# exo_sequencer.net
KiCad netlist of a schematic drawn in EAGLE
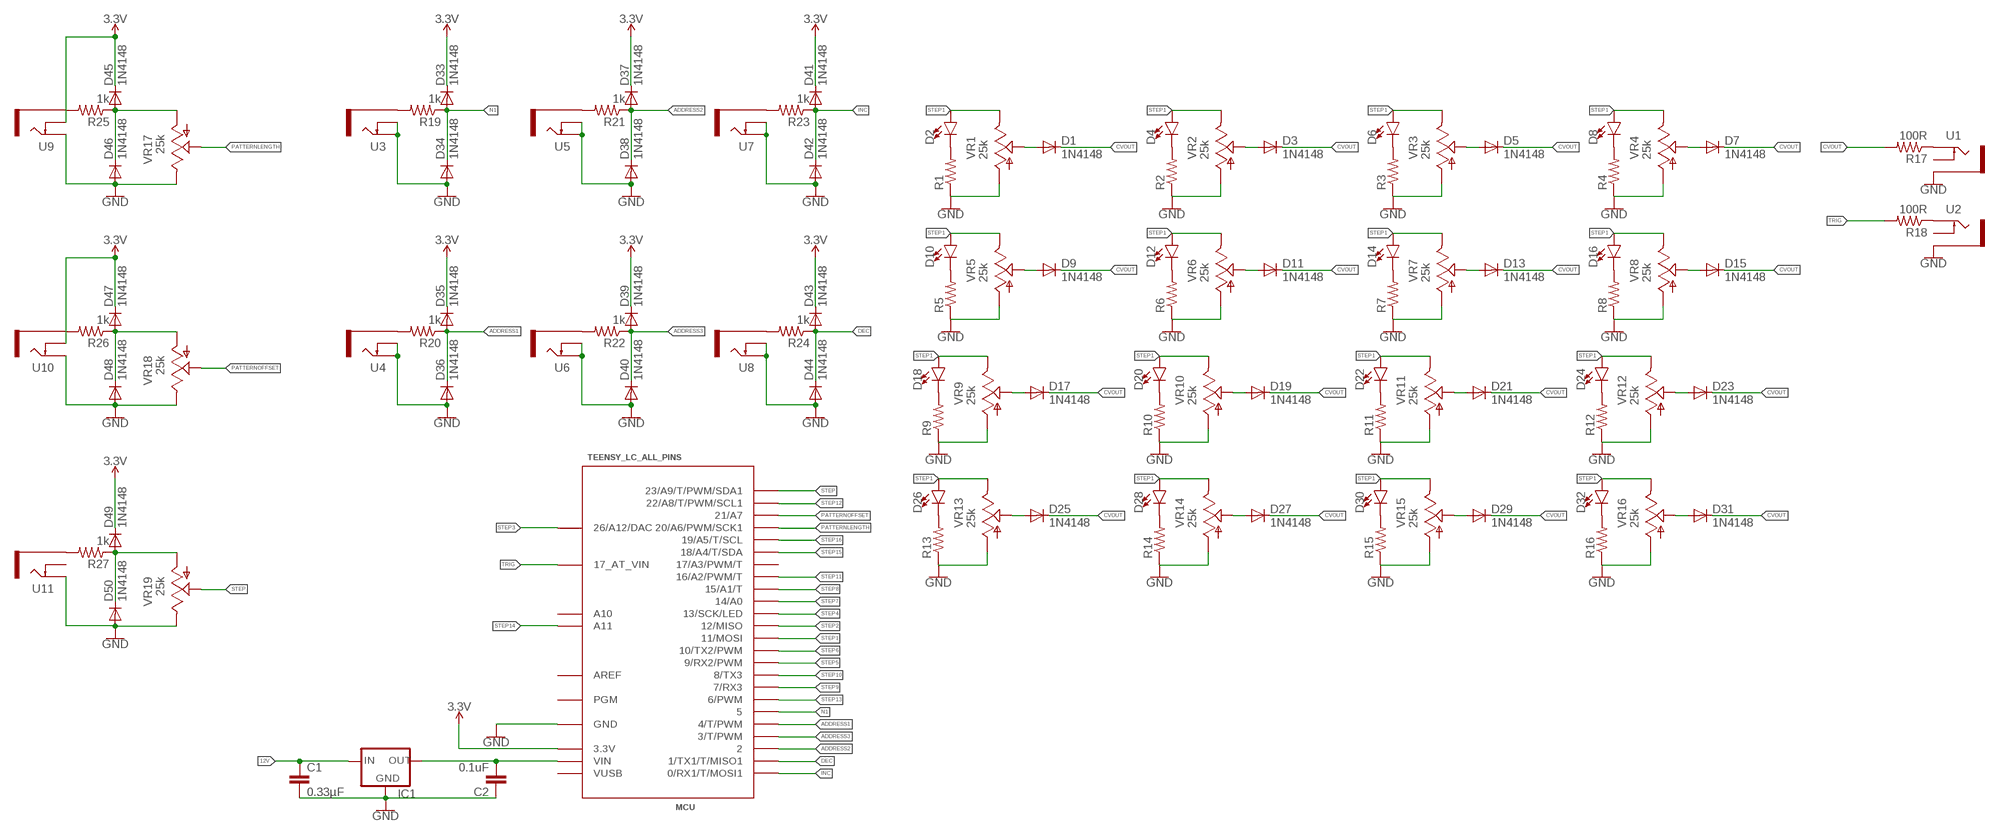
[diagram p0: schematic, sheet 1]

(export (version "E")
  (design (tool "Eeschema 10.0.6"))
  (components
    (comp (ref "C1")
      (value "0.33µF")
      (footprint "eagle-import:0805")
      (libsource (lib "eagle-import") (part "0.33UF/330NF-0805-50V-10%"))
    )
    (comp (ref "C2")
      (value "0.1uF")
      (footprint "eagle-import:0402")
      (libsource (lib "eagle-import") (part "0.1UF-0402-16V-10%"))
    )
    (comp (ref "D1")
      (value "1N4148")
      (footprint "eagle-import:DO35-7")
      (libsource (lib "eagle-import") (part "SMALL_DIODEDO35-7"))
    )
    (comp (ref "D2")
      (value "LED-3MM-NO_SILK")
      (footprint "eagle-import:LED_3MM-NS")
      (libsource (lib "eagle-import") (part "LED-3MM-NO_SILK"))
    )
    (comp (ref "D3")
      (value "1N4148")
      (footprint "eagle-import:DO35-7")
      (libsource (lib "eagle-import") (part "SMALL_DIODEDO35-7"))
    )
    (comp (ref "D4")
      (value "LED-3MM-NO_SILK")
      (footprint "eagle-import:LED_3MM-NS")
      (libsource (lib "eagle-import") (part "LED-3MM-NO_SILK"))
    )
    (comp (ref "D5")
      (value "1N4148")
      (footprint "eagle-import:DO35-7")
      (libsource (lib "eagle-import") (part "SMALL_DIODEDO35-7"))
    )
    (comp (ref "D6")
      (value "LED-3MM-NO_SILK")
      (footprint "eagle-import:LED_3MM-NS")
      (libsource (lib "eagle-import") (part "LED-3MM-NO_SILK"))
    )
    (comp (ref "D7")
      (value "1N4148")
      (footprint "eagle-import:DO35-7")
      (libsource (lib "eagle-import") (part "SMALL_DIODEDO35-7"))
    )
    (comp (ref "D8")
      (value "LED-3MM-NO_SILK")
      (footprint "eagle-import:LED_3MM-NS")
      (libsource (lib "eagle-import") (part "LED-3MM-NO_SILK"))
    )
    (comp (ref "D9")
      (value "1N4148")
      (footprint "eagle-import:DO35-7")
      (libsource (lib "eagle-import") (part "SMALL_DIODEDO35-7"))
    )
    (comp (ref "D10")
      (value "LED-3MM-NO_SILK")
      (footprint "eagle-import:LED_3MM-NS")
      (libsource (lib "eagle-import") (part "LED-3MM-NO_SILK"))
    )
    (comp (ref "D11")
      (value "1N4148")
      (footprint "eagle-import:DO35-7")
      (libsource (lib "eagle-import") (part "SMALL_DIODEDO35-7"))
    )
    (comp (ref "D12")
      (value "LED-3MM-NO_SILK")
      (footprint "eagle-import:LED_3MM-NS")
      (libsource (lib "eagle-import") (part "LED-3MM-NO_SILK"))
    )
    (comp (ref "D13")
      (value "1N4148")
      (footprint "eagle-import:DO35-7")
      (libsource (lib "eagle-import") (part "SMALL_DIODEDO35-7"))
    )
    (comp (ref "D14")
      (value "LED-3MM-NO_SILK")
      (footprint "eagle-import:LED_3MM-NS")
      (libsource (lib "eagle-import") (part "LED-3MM-NO_SILK"))
    )
    (comp (ref "D15")
      (value "1N4148")
      (footprint "eagle-import:DO35-7")
      (libsource (lib "eagle-import") (part "SMALL_DIODEDO35-7"))
    )
    (comp (ref "D16")
      (value "LED-3MM-NO_SILK")
      (footprint "eagle-import:LED_3MM-NS")
      (libsource (lib "eagle-import") (part "LED-3MM-NO_SILK"))
    )
    (comp (ref "D17")
      (value "1N4148")
      (footprint "eagle-import:DO35-7")
      (libsource (lib "eagle-import") (part "SMALL_DIODEDO35-7"))
    )
    (comp (ref "D18")
      (value "LED-3MM-NO_SILK")
      (footprint "eagle-import:LED_3MM-NS")
      (libsource (lib "eagle-import") (part "LED-3MM-NO_SILK"))
    )
    (comp (ref "D19")
      (value "1N4148")
      (footprint "eagle-import:DO35-7")
      (libsource (lib "eagle-import") (part "SMALL_DIODEDO35-7"))
    )
    (comp (ref "D20")
      (value "LED-3MM-NO_SILK")
      (footprint "eagle-import:LED_3MM-NS")
      (libsource (lib "eagle-import") (part "LED-3MM-NO_SILK"))
    )
    (comp (ref "D21")
      (value "1N4148")
      (footprint "eagle-import:DO35-7")
      (libsource (lib "eagle-import") (part "SMALL_DIODEDO35-7"))
    )
    (comp (ref "D22")
      (value "LED-3MM-NO_SILK")
      (footprint "eagle-import:LED_3MM-NS")
      (libsource (lib "eagle-import") (part "LED-3MM-NO_SILK"))
    )
    (comp (ref "D23")
      (value "1N4148")
      (footprint "eagle-import:DO35-7")
      (libsource (lib "eagle-import") (part "SMALL_DIODEDO35-7"))
    )
    (comp (ref "D24")
      (value "LED-3MM-NO_SILK")
      (footprint "eagle-import:LED_3MM-NS")
      (libsource (lib "eagle-import") (part "LED-3MM-NO_SILK"))
    )
    (comp (ref "D25")
      (value "1N4148")
      (footprint "eagle-import:DO35-7")
      (libsource (lib "eagle-import") (part "SMALL_DIODEDO35-7"))
    )
    (comp (ref "D26")
      (value "LED-3MM-NO_SILK")
      (footprint "eagle-import:LED_3MM-NS")
      (libsource (lib "eagle-import") (part "LED-3MM-NO_SILK"))
    )
    (comp (ref "D27")
      (value "1N4148")
      (footprint "eagle-import:DO35-7")
      (libsource (lib "eagle-import") (part "SMALL_DIODEDO35-7"))
    )
    (comp (ref "D28")
      (value "LED-3MM-NO_SILK")
      (footprint "eagle-import:LED_3MM-NS")
      (libsource (lib "eagle-import") (part "LED-3MM-NO_SILK"))
    )
    (comp (ref "D29")
      (value "1N4148")
      (footprint "eagle-import:DO35-7")
      (libsource (lib "eagle-import") (part "SMALL_DIODEDO35-7"))
    )
    (comp (ref "D30")
      (value "LED-3MM-NO_SILK")
      (footprint "eagle-import:LED_3MM-NS")
      (libsource (lib "eagle-import") (part "LED-3MM-NO_SILK"))
    )
    (comp (ref "D31")
      (value "1N4148")
      (footprint "eagle-import:DO35-7")
      (libsource (lib "eagle-import") (part "SMALL_DIODEDO35-7"))
    )
    (comp (ref "D32")
      (value "LED-3MM-NO_SILK")
      (footprint "eagle-import:LED_3MM-NS")
      (libsource (lib "eagle-import") (part "LED-3MM-NO_SILK"))
    )
    (comp (ref "D33")
      (value "1N4148")
      (footprint "eagle-import:DO35-7")
      (libsource (lib "eagle-import") (part "SMALL_DIODEDO35-7"))
    )
    (comp (ref "D34")
      (value "1N4148")
      (footprint "eagle-import:DO35-7")
      (libsource (lib "eagle-import") (part "SMALL_DIODEDO35-7"))
    )
    (comp (ref "D35")
      (value "1N4148")
      (footprint "eagle-import:DO35-7")
      (libsource (lib "eagle-import") (part "SMALL_DIODEDO35-7"))
    )
    (comp (ref "D36")
      (value "1N4148")
      (footprint "eagle-import:DO35-7")
      (libsource (lib "eagle-import") (part "SMALL_DIODEDO35-7"))
    )
    (comp (ref "D37")
      (value "1N4148")
      (footprint "eagle-import:DO35-7")
      (libsource (lib "eagle-import") (part "SMALL_DIODEDO35-7"))
    )
    (comp (ref "D38")
      (value "1N4148")
      (footprint "eagle-import:DO35-7")
      (libsource (lib "eagle-import") (part "SMALL_DIODEDO35-7"))
    )
    (comp (ref "D39")
      (value "1N4148")
      (footprint "eagle-import:DO35-7")
      (libsource (lib "eagle-import") (part "SMALL_DIODEDO35-7"))
    )
    (comp (ref "D40")
      (value "1N4148")
      (footprint "eagle-import:DO35-7")
      (libsource (lib "eagle-import") (part "SMALL_DIODEDO35-7"))
    )
    (comp (ref "D41")
      (value "1N4148")
      (footprint "eagle-import:DO35-7")
      (libsource (lib "eagle-import") (part "SMALL_DIODEDO35-7"))
    )
    (comp (ref "D42")
      (value "1N4148")
      (footprint "eagle-import:DO35-7")
      (libsource (lib "eagle-import") (part "SMALL_DIODEDO35-7"))
    )
    (comp (ref "D43")
      (value "1N4148")
      (footprint "eagle-import:DO35-7")
      (libsource (lib "eagle-import") (part "SMALL_DIODEDO35-7"))
    )
    (comp (ref "D44")
      (value "1N4148")
      (footprint "eagle-import:DO35-7")
      (libsource (lib "eagle-import") (part "SMALL_DIODEDO35-7"))
    )
    (comp (ref "D45")
      (value "1N4148")
      (footprint "eagle-import:DO35-7")
      (libsource (lib "eagle-import") (part "SMALL_DIODEDO35-7"))
    )
    (comp (ref "D46")
      (value "1N4148")
      (footprint "eagle-import:DO35-7")
      (libsource (lib "eagle-import") (part "SMALL_DIODEDO35-7"))
    )
    (comp (ref "D47")
      (value "1N4148")
      (footprint "eagle-import:DO35-7")
      (libsource (lib "eagle-import") (part "SMALL_DIODEDO35-7"))
    )
    (comp (ref "D48")
      (value "1N4148")
      (footprint "eagle-import:DO35-7")
      (libsource (lib "eagle-import") (part "SMALL_DIODEDO35-7"))
    )
    (comp (ref "D49")
      (value "1N4148")
      (footprint "eagle-import:DO35-7")
      (libsource (lib "eagle-import") (part "SMALL_DIODEDO35-7"))
    )
    (comp (ref "D50")
      (value "1N4148")
      (footprint "eagle-import:DO35-7")
      (libsource (lib "eagle-import") (part "SMALL_DIODEDO35-7"))
    )
    (comp (ref "IC1")
      (value "78MXXL")
      (footprint "eagle-import:78MXXL")
      (libsource (lib "eagle-import") (part "78MXXL"))
    )
    (comp (ref "MCU")
      (value "TEENSY_LC_ALL_PINS")
      (footprint "eagle-import:TEENSY_3.0-3.2&LC_ALL_PINS")
      (libsource (lib "eagle-import") (part "TEENSY_LC_ALL_PINS"))
    )
    (comp (ref "R1")
      (value "R-US_0204/7")
      (footprint "eagle-import:0204_7")
      (libsource (lib "eagle-import") (part "R-US_0204/7"))
    )
    (comp (ref "R2")
      (value "R-US_0204/7")
      (footprint "eagle-import:0204_7")
      (libsource (lib "eagle-import") (part "R-US_0204/7"))
    )
    (comp (ref "R3")
      (value "R-US_0204/7")
      (footprint "eagle-import:0204_7")
      (libsource (lib "eagle-import") (part "R-US_0204/7"))
    )
    (comp (ref "R4")
      (value "R-US_0204/7")
      (footprint "eagle-import:0204_7")
      (libsource (lib "eagle-import") (part "R-US_0204/7"))
    )
    (comp (ref "R5")
      (value "R-US_0204/7")
      (footprint "eagle-import:0204_7")
      (libsource (lib "eagle-import") (part "R-US_0204/7"))
    )
    (comp (ref "R6")
      (value "R-US_0204/7")
      (footprint "eagle-import:0204_7")
      (libsource (lib "eagle-import") (part "R-US_0204/7"))
    )
    (comp (ref "R7")
      (value "R-US_0204/7")
      (footprint "eagle-import:0204_7")
      (libsource (lib "eagle-import") (part "R-US_0204/7"))
    )
    (comp (ref "R8")
      (value "R-US_0204/7")
      (footprint "eagle-import:0204_7")
      (libsource (lib "eagle-import") (part "R-US_0204/7"))
    )
    (comp (ref "R9")
      (value "R-US_0204/7")
      (footprint "eagle-import:0204_7")
      (libsource (lib "eagle-import") (part "R-US_0204/7"))
    )
    (comp (ref "R10")
      (value "R-US_0204/7")
      (footprint "eagle-import:0204_7")
      (libsource (lib "eagle-import") (part "R-US_0204/7"))
    )
    (comp (ref "R11")
      (value "R-US_0204/7")
      (footprint "eagle-import:0204_7")
      (libsource (lib "eagle-import") (part "R-US_0204/7"))
    )
    (comp (ref "R12")
      (value "R-US_0204/7")
      (footprint "eagle-import:0204_7")
      (libsource (lib "eagle-import") (part "R-US_0204/7"))
    )
    (comp (ref "R13")
      (value "R-US_0204/7")
      (footprint "eagle-import:0204_7")
      (libsource (lib "eagle-import") (part "R-US_0204/7"))
    )
    (comp (ref "R14")
      (value "R-US_0204/7")
      (footprint "eagle-import:0204_7")
      (libsource (lib "eagle-import") (part "R-US_0204/7"))
    )
    (comp (ref "R15")
      (value "R-US_0204/7")
      (footprint "eagle-import:0204_7")
      (libsource (lib "eagle-import") (part "R-US_0204/7"))
    )
    (comp (ref "R16")
      (value "R-US_0204/7")
      (footprint "eagle-import:0204_7")
      (libsource (lib "eagle-import") (part "R-US_0204/7"))
    )
    (comp (ref "R17")
      (value "100R")
      (footprint "eagle-import:0204_7")
      (libsource (lib "eagle-import") (part "R-US_0204/7"))
    )
    (comp (ref "R18")
      (value "100R")
      (footprint "eagle-import:0204_7")
      (libsource (lib "eagle-import") (part "R-US_0204/7"))
    )
    (comp (ref "R19")
      (value "1k")
      (footprint "eagle-import:0204_7")
      (libsource (lib "eagle-import") (part "R-US_0204/7"))
    )
    (comp (ref "R20")
      (value "1k")
      (footprint "eagle-import:0204_7")
      (libsource (lib "eagle-import") (part "R-US_0204/7"))
    )
    (comp (ref "R21")
      (value "1k")
      (footprint "eagle-import:0204_7")
      (libsource (lib "eagle-import") (part "R-US_0204/7"))
    )
    (comp (ref "R22")
      (value "1k")
      (footprint "eagle-import:0204_7")
      (libsource (lib "eagle-import") (part "R-US_0204/7"))
    )
    (comp (ref "R23")
      (value "1k")
      (footprint "eagle-import:0204_7")
      (libsource (lib "eagle-import") (part "R-US_0204/7"))
    )
    (comp (ref "R24")
      (value "1k")
      (footprint "eagle-import:0204_7")
      (libsource (lib "eagle-import") (part "R-US_0204/7"))
    )
    (comp (ref "R25")
      (value "1k")
      (footprint "eagle-import:0204_7")
      (libsource (lib "eagle-import") (part "R-US_0204/7"))
    )
    (comp (ref "R26")
      (value "1k")
      (footprint "eagle-import:0204_7")
      (libsource (lib "eagle-import") (part "R-US_0204/7"))
    )
    (comp (ref "R27")
      (value "1k")
      (footprint "eagle-import:0204_7")
      (libsource (lib "eagle-import") (part "R-US_0204/7"))
    )
    (comp (ref "U1")
      (value "THONKICONNNEW")
      (footprint "eagle-import:WQP-PJ301M-12_JACK")
      (libsource (lib "eagle-import") (part "THONKICONNNEW"))
    )
    (comp (ref "U2")
      (value "THONKICONNNEW")
      (footprint "eagle-import:WQP-PJ301M-12_JACK")
      (libsource (lib "eagle-import") (part "THONKICONNNEW"))
    )
    (comp (ref "U3")
      (value "THONKICONNNEW")
      (footprint "eagle-import:WQP-PJ301M-12_JACK")
      (libsource (lib "eagle-import") (part "THONKICONNNEW"))
    )
    (comp (ref "U4")
      (value "THONKICONNNEW")
      (footprint "eagle-import:WQP-PJ301M-12_JACK")
      (libsource (lib "eagle-import") (part "THONKICONNNEW"))
    )
    (comp (ref "U5")
      (value "THONKICONNNEW")
      (footprint "eagle-import:WQP-PJ301M-12_JACK")
      (libsource (lib "eagle-import") (part "THONKICONNNEW"))
    )
    (comp (ref "U6")
      (value "THONKICONNNEW")
      (footprint "eagle-import:WQP-PJ301M-12_JACK")
      (libsource (lib "eagle-import") (part "THONKICONNNEW"))
    )
    (comp (ref "U7")
      (value "THONKICONNNEW")
      (footprint "eagle-import:WQP-PJ301M-12_JACK")
      (libsource (lib "eagle-import") (part "THONKICONNNEW"))
    )
    (comp (ref "U8")
      (value "THONKICONNNEW")
      (footprint "eagle-import:WQP-PJ301M-12_JACK")
      (libsource (lib "eagle-import") (part "THONKICONNNEW"))
    )
    (comp (ref "U9")
      (value "THONKICONNNEW")
      (footprint "eagle-import:WQP-PJ301M-12_JACK")
      (libsource (lib "eagle-import") (part "THONKICONNNEW"))
    )
    (comp (ref "U10")
      (value "THONKICONNNEW")
      (footprint "eagle-import:WQP-PJ301M-12_JACK")
      (libsource (lib "eagle-import") (part "THONKICONNNEW"))
    )
    (comp (ref "U11")
      (value "THONKICONNNEW")
      (footprint "eagle-import:WQP-PJ301M-12_JACK")
      (libsource (lib "eagle-import") (part "THONKICONNNEW"))
    )
    (comp (ref "VR1")
      (value "25k")
      (footprint "eagle-import:9MM_SNAP-IN_POT")
      (libsource (lib "eagle-import") (part "9MM_SNAP-IN_POT_"))
    )
    (comp (ref "VR2")
      (value "25k")
      (footprint "eagle-import:9MM_SNAP-IN_POT")
      (libsource (lib "eagle-import") (part "9MM_SNAP-IN_POT_"))
    )
    (comp (ref "VR3")
      (value "25k")
      (footprint "eagle-import:9MM_SNAP-IN_POT")
      (libsource (lib "eagle-import") (part "9MM_SNAP-IN_POT_"))
    )
    (comp (ref "VR4")
      (value "25k")
      (footprint "eagle-import:9MM_SNAP-IN_POT")
      (libsource (lib "eagle-import") (part "9MM_SNAP-IN_POT_"))
    )
    (comp (ref "VR5")
      (value "25k")
      (footprint "eagle-import:9MM_SNAP-IN_POT")
      (libsource (lib "eagle-import") (part "9MM_SNAP-IN_POT_"))
    )
    (comp (ref "VR6")
      (value "25k")
      (footprint "eagle-import:9MM_SNAP-IN_POT")
      (libsource (lib "eagle-import") (part "9MM_SNAP-IN_POT_"))
    )
    (comp (ref "VR7")
      (value "25k")
      (footprint "eagle-import:9MM_SNAP-IN_POT")
      (libsource (lib "eagle-import") (part "9MM_SNAP-IN_POT_"))
    )
    (comp (ref "VR8")
      (value "25k")
      (footprint "eagle-import:9MM_SNAP-IN_POT")
      (libsource (lib "eagle-import") (part "9MM_SNAP-IN_POT_"))
    )
    (comp (ref "VR9")
      (value "25k")
      (footprint "eagle-import:9MM_SNAP-IN_POT")
      (libsource (lib "eagle-import") (part "9MM_SNAP-IN_POT_"))
    )
    (comp (ref "VR10")
      (value "25k")
      (footprint "eagle-import:9MM_SNAP-IN_POT")
      (libsource (lib "eagle-import") (part "9MM_SNAP-IN_POT_"))
    )
    (comp (ref "VR11")
      (value "25k")
      (footprint "eagle-import:9MM_SNAP-IN_POT")
      (libsource (lib "eagle-import") (part "9MM_SNAP-IN_POT_"))
    )
    (comp (ref "VR12")
      (value "25k")
      (footprint "eagle-import:9MM_SNAP-IN_POT")
      (libsource (lib "eagle-import") (part "9MM_SNAP-IN_POT_"))
    )
    (comp (ref "VR13")
      (value "25k")
      (footprint "eagle-import:9MM_SNAP-IN_POT")
      (libsource (lib "eagle-import") (part "9MM_SNAP-IN_POT_"))
    )
    (comp (ref "VR14")
      (value "25k")
      (footprint "eagle-import:9MM_SNAP-IN_POT")
      (libsource (lib "eagle-import") (part "9MM_SNAP-IN_POT_"))
    )
    (comp (ref "VR15")
      (value "25k")
      (footprint "eagle-import:9MM_SNAP-IN_POT")
      (libsource (lib "eagle-import") (part "9MM_SNAP-IN_POT_"))
    )
    (comp (ref "VR16")
      (value "25k")
      (footprint "eagle-import:9MM_SNAP-IN_POT")
      (libsource (lib "eagle-import") (part "9MM_SNAP-IN_POT_"))
    )
    (comp (ref "VR17")
      (value "25k")
      (footprint "eagle-import:9MM_SNAP-IN_POT")
      (libsource (lib "eagle-import") (part "9MM_SNAP-IN_POT_"))
    )
    (comp (ref "VR18")
      (value "25k")
      (footprint "eagle-import:9MM_SNAP-IN_POT")
      (libsource (lib "eagle-import") (part "9MM_SNAP-IN_POT_"))
    )
    (comp (ref "VR19")
      (value "25k")
      (footprint "eagle-import:9MM_SNAP-IN_POT")
      (libsource (lib "eagle-import") (part "9MM_SNAP-IN_POT_"))
    )
  )
  (nets
    (net (code "1") (name "/AREF") (class "Default")
      (node (ref "MCU") (pin "AREF") (pinfunction "AREF_AREF") (pintype "power_in"))
    )
    (net (code "2") (name "/VUSB") (class "Default")
      (node (ref "MCU") (pin "VUSB") (pinfunction "VUSB_VUSB") (pintype "power_in"))
    )
    (net (code "3") (name "3.3V") (class "Default")
      (node (ref "D33") (pin "C") (pinfunction "C_C") (pintype "passive"))
      (node (ref "D35") (pin "C") (pinfunction "C_C") (pintype "passive"))
      (node (ref "D37") (pin "C") (pinfunction "C_C") (pintype "passive"))
      (node (ref "D39") (pin "C") (pinfunction "C_C") (pintype "passive"))
      (node (ref "D41") (pin "C") (pinfunction "C_C") (pintype "passive"))
      (node (ref "D43") (pin "C") (pinfunction "C_C") (pintype "passive"))
      (node (ref "D45") (pin "C") (pinfunction "C_C") (pintype "passive"))
      (node (ref "D47") (pin "C") (pinfunction "C_C") (pintype "passive"))
      (node (ref "D49") (pin "C") (pinfunction "C_C") (pintype "passive"))
      (node (ref "MCU") (pin "3.3V") (pinfunction "3.3V_3.3V") (pintype "power_in"))
      (node (ref "MCU") (pin "3.3V1") (pinfunction "3.3V_3.3V1") (pintype "power_in"))
      (node (ref "U10") (pin "P$2_SWITCH") (pinfunction "SWITCH_P$2_SWITCH") (pintype "passive"))
      (node (ref "U9") (pin "P$2_SWITCH") (pinfunction "SWITCH_P$2_SWITCH") (pintype "passive"))
    )
    (net (code "4") (name "12V") (class "Default")
      (node (ref "C1") (pin "1") (pinfunction "1_1") (pintype "passive"))
      (node (ref "IC1") (pin "IN") (pinfunction "IN_IN") (pintype "input"))
    )
    (net (code "5") (name "ADDRESS1") (class "Default")
      (node (ref "D35") (pin "A") (pinfunction "A_A") (pintype "passive"))
      (node (ref "D36") (pin "C") (pinfunction "C_C") (pintype "passive"))
      (node (ref "MCU") (pin "4") (pinfunction "4/T/PWM_4") (pintype "bidirectional"))
      (node (ref "R20") (pin "1") (pinfunction "1_1") (pintype "passive"))
    )
    (net (code "6") (name "ADDRESS2") (class "Default")
      (node (ref "D37") (pin "A") (pinfunction "A_A") (pintype "passive"))
      (node (ref "D38") (pin "C") (pinfunction "C_C") (pintype "passive"))
      (node (ref "MCU") (pin "2") (pinfunction "2_2") (pintype "bidirectional"))
      (node (ref "R21") (pin "1") (pinfunction "1_1") (pintype "passive"))
    )
    (net (code "7") (name "ADDRESS3") (class "Default")
      (node (ref "D39") (pin "A") (pinfunction "A_A") (pintype "passive"))
      (node (ref "D40") (pin "C") (pinfunction "C_C") (pintype "passive"))
      (node (ref "MCU") (pin "3") (pinfunction "3/T/PWM_3") (pintype "bidirectional"))
      (node (ref "R22") (pin "1") (pinfunction "1_1") (pintype "passive"))
    )
    (net (code "8") (name "CVOUT") (class "Default")
      (node (ref "D1") (pin "C") (pinfunction "C_C") (pintype "passive"))
      (node (ref "D11") (pin "C") (pinfunction "C_C") (pintype "passive"))
      (node (ref "D13") (pin "C") (pinfunction "C_C") (pintype "passive"))
      (node (ref "D15") (pin "C") (pinfunction "C_C") (pintype "passive"))
      (node (ref "D17") (pin "C") (pinfunction "C_C") (pintype "passive"))
      (node (ref "D19") (pin "C") (pinfunction "C_C") (pintype "passive"))
      (node (ref "D21") (pin "C") (pinfunction "C_C") (pintype "passive"))
      (node (ref "D23") (pin "C") (pinfunction "C_C") (pintype "passive"))
      (node (ref "D25") (pin "C") (pinfunction "C_C") (pintype "passive"))
      (node (ref "D27") (pin "C") (pinfunction "C_C") (pintype "passive"))
      (node (ref "D29") (pin "C") (pinfunction "C_C") (pintype "passive"))
      (node (ref "D3") (pin "C") (pinfunction "C_C") (pintype "passive"))
      (node (ref "D31") (pin "C") (pinfunction "C_C") (pintype "passive"))
      (node (ref "D5") (pin "C") (pinfunction "C_C") (pintype "passive"))
      (node (ref "D7") (pin "C") (pinfunction "C_C") (pintype "passive"))
      (node (ref "D9") (pin "C") (pinfunction "C_C") (pintype "passive"))
      (node (ref "R17") (pin "2") (pinfunction "2_2") (pintype "passive"))
    )
    (net (code "9") (name "DEC") (class "Default")
      (node (ref "D43") (pin "A") (pinfunction "A_A") (pintype "passive"))
      (node (ref "D44") (pin "C") (pinfunction "C_C") (pintype "passive"))
      (node (ref "MCU") (pin "1") (pinfunction "1/TX1/T/MISO1_1") (pintype "bidirectional"))
      (node (ref "R24") (pin "1") (pinfunction "1_1") (pintype "passive"))
    )
    (net (code "10") (name "GND") (class "Default")
      (node (ref "C1") (pin "2") (pinfunction "2_2") (pintype "passive"))
      (node (ref "C2") (pin "1") (pinfunction "1_1") (pintype "passive"))
      (node (ref "D34") (pin "A") (pinfunction "A_A") (pintype "passive"))
      (node (ref "D36") (pin "A") (pinfunction "A_A") (pintype "passive"))
      (node (ref "D38") (pin "A") (pinfunction "A_A") (pintype "passive"))
      (node (ref "D40") (pin "A") (pinfunction "A_A") (pintype "passive"))
      (node (ref "D42") (pin "A") (pinfunction "A_A") (pintype "passive"))
      (node (ref "D44") (pin "A") (pinfunction "A_A") (pintype "passive"))
      (node (ref "D46") (pin "A") (pinfunction "A_A") (pintype "passive"))
      (node (ref "D48") (pin "A") (pinfunction "A_A") (pintype "passive"))
      (node (ref "D50") (pin "A") (pinfunction "A_A") (pintype "passive"))
      (node (ref "IC1") (pin "GND") (pinfunction "GND_GND") (pintype "input"))
      (node (ref "MCU") (pin "AGND") (pinfunction "GND_AGND") (pintype "power_in"))
      (node (ref "MCU") (pin "GND") (pinfunction "GND_GND") (pintype "power_in"))
      (node (ref "MCU") (pin "GND1") (pinfunction "GND_GND1") (pintype "power_in"))
      (node (ref "R1") (pin "1") (pinfunction "1_1") (pintype "passive"))
      (node (ref "R10") (pin "1") (pinfunction "1_1") (pintype "passive"))
      (node (ref "R11") (pin "1") (pinfunction "1_1") (pintype "passive"))
      (node (ref "R12") (pin "1") (pinfunction "1_1") (pintype "passive"))
      (node (ref "R13") (pin "1") (pinfunction "1_1") (pintype "passive"))
      (node (ref "R14") (pin "1") (pinfunction "1_1") (pintype "passive"))
      (node (ref "R15") (pin "1") (pinfunction "1_1") (pintype "passive"))
      (node (ref "R16") (pin "1") (pinfunction "1_1") (pintype "passive"))
      (node (ref "R2") (pin "1") (pinfunction "1_1") (pintype "passive"))
      (node (ref "R3") (pin "1") (pinfunction "1_1") (pintype "passive"))
      (node (ref "R4") (pin "1") (pinfunction "1_1") (pintype "passive"))
      (node (ref "R5") (pin "1") (pinfunction "1_1") (pintype "passive"))
      (node (ref "R6") (pin "1") (pinfunction "1_1") (pintype "passive"))
      (node (ref "R7") (pin "1") (pinfunction "1_1") (pintype "passive"))
      (node (ref "R8") (pin "1") (pinfunction "1_1") (pintype "passive"))
      (node (ref "R9") (pin "1") (pinfunction "1_1") (pintype "passive"))
      (node (ref "U1") (pin "P$3_SLEEVE") (pinfunction "SLEEVE_P$3_SLEEVE") (pintype "passive"))
      (node (ref "U10") (pin "P$1_TIP") (pinfunction "TIP_P$1_TIP") (pintype "passive"))
      (node (ref "U11") (pin "P$1_TIP") (pinfunction "TIP_P$1_TIP") (pintype "passive"))
      (node (ref "U2") (pin "P$3_SLEEVE") (pinfunction "SLEEVE_P$3_SLEEVE") (pintype "passive"))
      (node (ref "U3") (pin "P$1_TIP") (pinfunction "TIP_P$1_TIP") (pintype "passive"))
      (node (ref "U3") (pin "P$2_SWITCH") (pinfunction "SWITCH_P$2_SWITCH") (pintype "passive"))
      (node (ref "U4") (pin "P$1_TIP") (pinfunction "TIP_P$1_TIP") (pintype "passive"))
      (node (ref "U4") (pin "P$2_SWITCH") (pinfunction "SWITCH_P$2_SWITCH") (pintype "passive"))
      (node (ref "U5") (pin "P$1_TIP") (pinfunction "TIP_P$1_TIP") (pintype "passive"))
      (node (ref "U5") (pin "P$2_SWITCH") (pinfunction "SWITCH_P$2_SWITCH") (pintype "passive"))
      (node (ref "U6") (pin "P$1_TIP") (pinfunction "TIP_P$1_TIP") (pintype "passive"))
      (node (ref "U6") (pin "P$2_SWITCH") (pinfunction "SWITCH_P$2_SWITCH") (pintype "passive"))
      (node (ref "U7") (pin "P$1_TIP") (pinfunction "TIP_P$1_TIP") (pintype "passive"))
      (node (ref "U7") (pin "P$2_SWITCH") (pinfunction "SWITCH_P$2_SWITCH") (pintype "passive"))
      (node (ref "U8") (pin "P$1_TIP") (pinfunction "TIP_P$1_TIP") (pintype "passive"))
      (node (ref "U8") (pin "P$2_SWITCH") (pinfunction "SWITCH_P$2_SWITCH") (pintype "passive"))
      (node (ref "U9") (pin "P$1_TIP") (pinfunction "TIP_P$1_TIP") (pintype "passive"))
      (node (ref "VR1") (pin "1") (pinfunction "A_1") (pintype "passive"))
      (node (ref "VR10") (pin "1") (pinfunction "A_1") (pintype "passive"))
      (node (ref "VR11") (pin "1") (pinfunction "A_1") (pintype "passive"))
      (node (ref "VR12") (pin "1") (pinfunction "A_1") (pintype "passive"))
      (node (ref "VR13") (pin "1") (pinfunction "A_1") (pintype "passive"))
      (node (ref "VR14") (pin "1") (pinfunction "A_1") (pintype "passive"))
      (node (ref "VR15") (pin "1") (pinfunction "A_1") (pintype "passive"))
      (node (ref "VR16") (pin "1") (pinfunction "A_1") (pintype "passive"))
      (node (ref "VR17") (pin "3") (pinfunction "E_3") (pintype "passive"))
      (node (ref "VR18") (pin "3") (pinfunction "E_3") (pintype "passive"))
      (node (ref "VR19") (pin "3") (pinfunction "E_3") (pintype "passive"))
      (node (ref "VR2") (pin "1") (pinfunction "A_1") (pintype "passive"))
      (node (ref "VR3") (pin "1") (pinfunction "A_1") (pintype "passive"))
      (node (ref "VR4") (pin "1") (pinfunction "A_1") (pintype "passive"))
      (node (ref "VR5") (pin "1") (pinfunction "A_1") (pintype "passive"))
      (node (ref "VR6") (pin "1") (pinfunction "A_1") (pintype "passive"))
      (node (ref "VR7") (pin "1") (pinfunction "A_1") (pintype "passive"))
      (node (ref "VR8") (pin "1") (pinfunction "A_1") (pintype "passive"))
      (node (ref "VR9") (pin "1") (pinfunction "A_1") (pintype "passive"))
    )
    (net (code "11") (name "INC") (class "Default")
      (node (ref "D41") (pin "A") (pinfunction "A_A") (pintype "passive"))
      (node (ref "D42") (pin "C") (pinfunction "C_C") (pintype "passive"))
      (node (ref "MCU") (pin "0") (pinfunction "0/RX1/T/MOSI1_0") (pintype "bidirectional"))
      (node (ref "R23") (pin "1") (pinfunction "1_1") (pintype "passive"))
    )
    (net (code "12") (name "N1") (class "Default")
      (node (ref "D33") (pin "A") (pinfunction "A_A") (pintype "passive"))
      (node (ref "D34") (pin "C") (pinfunction "C_C") (pintype "passive"))
      (node (ref "D45") (pin "A") (pinfunction "A_A") (pintype "passive"))
      (node (ref "D46") (pin "C") (pinfunction "C_C") (pintype "passive"))
      (node (ref "MCU") (pin "5") (pinfunction "5_5") (pintype "bidirectional"))
      (node (ref "R19") (pin "1") (pinfunction "1_1") (pintype "passive"))
      (node (ref "R25") (pin "1") (pinfunction "1_1") (pintype "passive"))
      (node (ref "VR17") (pin "1") (pinfunction "A_1") (pintype "passive"))
    )
    (net (code "13") (name "Net-(C2-Pad2)") (class "Default")
      (node (ref "C2") (pin "2") (pinfunction "2_2") (pintype "passive"))
      (node (ref "IC1") (pin "OUT") (pinfunction "OUT_OUT") (pintype "passive"))
      (node (ref "MCU") (pin "VIN") (pinfunction "VIN_VIN") (pintype "power_in"))
    )
    (net (code "14") (name "Net-(D2-C)") (class "Default")
      (node (ref "D2") (pin "K") (pinfunction "C_K") (pintype "passive"))
      (node (ref "R1") (pin "2") (pinfunction "2_2") (pintype "passive"))
    )
    (net (code "15") (name "Net-(D4-C)") (class "Default")
      (node (ref "D4") (pin "K") (pinfunction "C_K") (pintype "passive"))
      (node (ref "R2") (pin "2") (pinfunction "2_2") (pintype "passive"))
    )
    (net (code "16") (name "Net-(D6-C)") (class "Default")
      (node (ref "D6") (pin "K") (pinfunction "C_K") (pintype "passive"))
      (node (ref "R3") (pin "2") (pinfunction "2_2") (pintype "passive"))
    )
    (net (code "17") (name "Net-(D8-C)") (class "Default")
      (node (ref "D8") (pin "K") (pinfunction "C_K") (pintype "passive"))
      (node (ref "R4") (pin "2") (pinfunction "2_2") (pintype "passive"))
    )
    (net (code "18") (name "Net-(D10-C)") (class "Default")
      (node (ref "D10") (pin "K") (pinfunction "C_K") (pintype "passive"))
      (node (ref "R5") (pin "2") (pinfunction "2_2") (pintype "passive"))
    )
    (net (code "19") (name "Net-(D12-C)") (class "Default")
      (node (ref "D12") (pin "K") (pinfunction "C_K") (pintype "passive"))
      (node (ref "R6") (pin "2") (pinfunction "2_2") (pintype "passive"))
    )
    (net (code "20") (name "Net-(D14-C)") (class "Default")
      (node (ref "D14") (pin "K") (pinfunction "C_K") (pintype "passive"))
      (node (ref "R7") (pin "2") (pinfunction "2_2") (pintype "passive"))
    )
    (net (code "21") (name "Net-(D16-C)") (class "Default")
      (node (ref "D16") (pin "K") (pinfunction "C_K") (pintype "passive"))
      (node (ref "R8") (pin "2") (pinfunction "2_2") (pintype "passive"))
    )
    (net (code "22") (name "Net-(D18-C)") (class "Default")
      (node (ref "D18") (pin "K") (pinfunction "C_K") (pintype "passive"))
      (node (ref "R9") (pin "2") (pinfunction "2_2") (pintype "passive"))
    )
    (net (code "23") (name "Net-(D20-C)") (class "Default")
      (node (ref "D20") (pin "K") (pinfunction "C_K") (pintype "passive"))
      (node (ref "R10") (pin "2") (pinfunction "2_2") (pintype "passive"))
    )
    (net (code "24") (name "Net-(D22-C)") (class "Default")
      (node (ref "D22") (pin "K") (pinfunction "C_K") (pintype "passive"))
      (node (ref "R11") (pin "2") (pinfunction "2_2") (pintype "passive"))
    )
    (net (code "25") (name "Net-(D24-C)") (class "Default")
      (node (ref "D24") (pin "K") (pinfunction "C_K") (pintype "passive"))
      (node (ref "R12") (pin "2") (pinfunction "2_2") (pintype "passive"))
    )
    (net (code "26") (name "Net-(D26-C)") (class "Default")
      (node (ref "D26") (pin "K") (pinfunction "C_K") (pintype "passive"))
      (node (ref "R13") (pin "2") (pinfunction "2_2") (pintype "passive"))
    )
    (net (code "27") (name "Net-(D28-C)") (class "Default")
      (node (ref "D28") (pin "K") (pinfunction "C_K") (pintype "passive"))
      (node (ref "R14") (pin "2") (pinfunction "2_2") (pintype "passive"))
    )
    (net (code "28") (name "Net-(D30-C)") (class "Default")
      (node (ref "D30") (pin "K") (pinfunction "C_K") (pintype "passive"))
      (node (ref "R15") (pin "2") (pinfunction "2_2") (pintype "passive"))
    )
    (net (code "29") (name "Net-(D32-C)") (class "Default")
      (node (ref "D32") (pin "K") (pinfunction "C_K") (pintype "passive"))
      (node (ref "R16") (pin "2") (pinfunction "2_2") (pintype "passive"))
    )
    (net (code "30") (name "Net-(U1-TIP)") (class "Default")
      (node (ref "R17") (pin "1") (pinfunction "1_1") (pintype "passive"))
      (node (ref "U1") (pin "P$1_TIP") (pinfunction "TIP_P$1_TIP") (pintype "passive"))
    )
    (net (code "31") (name "Net-(U2-TIP)") (class "Default")
      (node (ref "R18") (pin "1") (pinfunction "1_1") (pintype "passive"))
      (node (ref "U2") (pin "P$1_TIP") (pinfunction "TIP_P$1_TIP") (pintype "passive"))
    )
    (net (code "32") (name "Net-(U3-SLEEVE)") (class "Default")
      (node (ref "R19") (pin "2") (pinfunction "2_2") (pintype "passive"))
      (node (ref "U3") (pin "P$3_SLEEVE") (pinfunction "SLEEVE_P$3_SLEEVE") (pintype "passive"))
    )
    (net (code "33") (name "Net-(U4-SLEEVE)") (class "Default")
      (node (ref "R20") (pin "2") (pinfunction "2_2") (pintype "passive"))
      (node (ref "U4") (pin "P$3_SLEEVE") (pinfunction "SLEEVE_P$3_SLEEVE") (pintype "passive"))
    )
    (net (code "34") (name "Net-(U5-SLEEVE)") (class "Default")
      (node (ref "R21") (pin "2") (pinfunction "2_2") (pintype "passive"))
      (node (ref "U5") (pin "P$3_SLEEVE") (pinfunction "SLEEVE_P$3_SLEEVE") (pintype "passive"))
    )
    (net (code "35") (name "Net-(U6-SLEEVE)") (class "Default")
      (node (ref "R22") (pin "2") (pinfunction "2_2") (pintype "passive"))
      (node (ref "U6") (pin "P$3_SLEEVE") (pinfunction "SLEEVE_P$3_SLEEVE") (pintype "passive"))
    )
    (net (code "36") (name "Net-(U7-SLEEVE)") (class "Default")
      (node (ref "R23") (pin "2") (pinfunction "2_2") (pintype "passive"))
      (node (ref "U7") (pin "P$3_SLEEVE") (pinfunction "SLEEVE_P$3_SLEEVE") (pintype "passive"))
    )
    (net (code "37") (name "Net-(U8-SLEEVE)") (class "Default")
      (node (ref "R24") (pin "2") (pinfunction "2_2") (pintype "passive"))
      (node (ref "U8") (pin "P$3_SLEEVE") (pinfunction "SLEEVE_P$3_SLEEVE") (pintype "passive"))
    )
    (net (code "38") (name "Net-(U9-SLEEVE)") (class "Default")
      (node (ref "R25") (pin "2") (pinfunction "2_2") (pintype "passive"))
      (node (ref "U9") (pin "P$3_SLEEVE") (pinfunction "SLEEVE_P$3_SLEEVE") (pintype "passive"))
    )
    (net (code "39") (name "Net-(U10-SLEEVE)") (class "Default")
      (node (ref "R26") (pin "2") (pinfunction "2_2") (pintype "passive"))
      (node (ref "U10") (pin "P$3_SLEEVE") (pinfunction "SLEEVE_P$3_SLEEVE") (pintype "passive"))
    )
    (net (code "40") (name "Net-(U11-SLEEVE)") (class "Default")
      (node (ref "R27") (pin "2") (pinfunction "2_2") (pintype "passive"))
      (node (ref "U11") (pin "P$3_SLEEVE") (pinfunction "SLEEVE_P$3_SLEEVE") (pintype "passive"))
    )
    (net (code "41") (name "Net-(VR1-S)") (class "Default")
      (node (ref "D1") (pin "A") (pinfunction "A_A") (pintype "passive"))
      (node (ref "VR1") (pin "2") (pinfunction "S_2") (pintype "passive"))
    )
    (net (code "42") (name "Net-(VR2-S)") (class "Default")
      (node (ref "D3") (pin "A") (pinfunction "A_A") (pintype "passive"))
      (node (ref "VR2") (pin "2") (pinfunction "S_2") (pintype "passive"))
    )
    (net (code "43") (name "Net-(VR3-S)") (class "Default")
      (node (ref "D5") (pin "A") (pinfunction "A_A") (pintype "passive"))
      (node (ref "VR3") (pin "2") (pinfunction "S_2") (pintype "passive"))
    )
    (net (code "44") (name "Net-(VR4-S)") (class "Default")
      (node (ref "D7") (pin "A") (pinfunction "A_A") (pintype "passive"))
      (node (ref "VR4") (pin "2") (pinfunction "S_2") (pintype "passive"))
    )
    (net (code "45") (name "Net-(VR5-S)") (class "Default")
      (node (ref "D9") (pin "A") (pinfunction "A_A") (pintype "passive"))
      (node (ref "VR5") (pin "2") (pinfunction "S_2") (pintype "passive"))
    )
    (net (code "46") (name "Net-(VR6-S)") (class "Default")
      (node (ref "D11") (pin "A") (pinfunction "A_A") (pintype "passive"))
      (node (ref "VR6") (pin "2") (pinfunction "S_2") (pintype "passive"))
    )
    (net (code "47") (name "Net-(VR7-S)") (class "Default")
      (node (ref "D13") (pin "A") (pinfunction "A_A") (pintype "passive"))
      (node (ref "VR7") (pin "2") (pinfunction "S_2") (pintype "passive"))
    )
    (net (code "48") (name "Net-(VR8-S)") (class "Default")
      (node (ref "D15") (pin "A") (pinfunction "A_A") (pintype "passive"))
      (node (ref "VR8") (pin "2") (pinfunction "S_2") (pintype "passive"))
    )
    (net (code "49") (name "Net-(VR9-S)") (class "Default")
      (node (ref "D17") (pin "A") (pinfunction "A_A") (pintype "passive"))
      (node (ref "VR9") (pin "2") (pinfunction "S_2") (pintype "passive"))
    )
    (net (code "50") (name "Net-(VR10-S)") (class "Default")
      (node (ref "D19") (pin "A") (pinfunction "A_A") (pintype "passive"))
      (node (ref "VR10") (pin "2") (pinfunction "S_2") (pintype "passive"))
    )
    (net (code "51") (name "Net-(VR11-S)") (class "Default")
      (node (ref "D21") (pin "A") (pinfunction "A_A") (pintype "passive"))
      (node (ref "VR11") (pin "2") (pinfunction "S_2") (pintype "passive"))
    )
    (net (code "52") (name "Net-(VR12-S)") (class "Default")
      (node (ref "D23") (pin "A") (pinfunction "A_A") (pintype "passive"))
      (node (ref "VR12") (pin "2") (pinfunction "S_2") (pintype "passive"))
    )
    (net (code "53") (name "Net-(VR13-S)") (class "Default")
      (node (ref "D25") (pin "A") (pinfunction "A_A") (pintype "passive"))
      (node (ref "VR13") (pin "2") (pinfunction "S_2") (pintype "passive"))
    )
    (net (code "54") (name "Net-(VR14-S)") (class "Default")
      (node (ref "D27") (pin "A") (pinfunction "A_A") (pintype "passive"))
      (node (ref "VR14") (pin "2") (pinfunction "S_2") (pintype "passive"))
    )
    (net (code "55") (name "Net-(VR15-S)") (class "Default")
      (node (ref "D29") (pin "A") (pinfunction "A_A") (pintype "passive"))
      (node (ref "VR15") (pin "2") (pinfunction "S_2") (pintype "passive"))
    )
    (net (code "56") (name "Net-(VR16-S)") (class "Default")
      (node (ref "D31") (pin "A") (pinfunction "A_A") (pintype "passive"))
      (node (ref "VR16") (pin "2") (pinfunction "S_2") (pintype "passive"))
    )
    (net (code "57") (name "Net-(VR18-A)") (class "Default")
      (node (ref "D47") (pin "A") (pinfunction "A_A") (pintype "passive"))
      (node (ref "D48") (pin "C") (pinfunction "C_C") (pintype "passive"))
      (node (ref "R26") (pin "1") (pinfunction "1_1") (pintype "passive"))
      (node (ref "VR18") (pin "1") (pinfunction "A_1") (pintype "passive"))
    )
    (net (code "58") (name "Net-(VR19-A)") (class "Default")
      (node (ref "D49") (pin "A") (pinfunction "A_A") (pintype "passive"))
      (node (ref "D50") (pin "C") (pinfunction "C_C") (pintype "passive"))
      (node (ref "R27") (pin "1") (pinfunction "1_1") (pintype "passive"))
      (node (ref "VR19") (pin "1") (pinfunction "A_1") (pintype "passive"))
    )
    (net (code "59") (name "PATTERNLENGTH") (class "Default")
      (node (ref "MCU") (pin "20/A6") (pinfunction "20/A6/PWM/SCK1_20/A6") (pintype "bidirectional"))
      (node (ref "VR17") (pin "2") (pinfunction "S_2") (pintype "passive"))
    )
    (net (code "60") (name "PATTERNOFFSET") (class "Default")
      (node (ref "MCU") (pin "21/A7") (pinfunction "21/A7_21/A7") (pintype "bidirectional"))
      (node (ref "VR18") (pin "2") (pinfunction "S_2") (pintype "passive"))
    )
    (net (code "61") (name "STEP") (class "Default")
      (node (ref "MCU") (pin "23/A9") (pinfunction "23/A9/T/PWM/SDA1_23/A9") (pintype "bidirectional"))
      (node (ref "VR19") (pin "2") (pinfunction "S_2") (pintype "passive"))
    )
    (net (code "62") (name "STEP1") (class "Default")
      (node (ref "D10") (pin "A") (pinfunction "A_A") (pintype "passive"))
      (node (ref "D12") (pin "A") (pinfunction "A_A") (pintype "passive"))
      (node (ref "D14") (pin "A") (pinfunction "A_A") (pintype "passive"))
      (node (ref "D16") (pin "A") (pinfunction "A_A") (pintype "passive"))
      (node (ref "D18") (pin "A") (pinfunction "A_A") (pintype "passive"))
      (node (ref "D2") (pin "A") (pinfunction "A_A") (pintype "passive"))
      (node (ref "D20") (pin "A") (pinfunction "A_A") (pintype "passive"))
      (node (ref "D22") (pin "A") (pinfunction "A_A") (pintype "passive"))
      (node (ref "D24") (pin "A") (pinfunction "A_A") (pintype "passive"))
      (node (ref "D26") (pin "A") (pinfunction "A_A") (pintype "passive"))
      (node (ref "D28") (pin "A") (pinfunction "A_A") (pintype "passive"))
      (node (ref "D30") (pin "A") (pinfunction "A_A") (pintype "passive"))
      (node (ref "D32") (pin "A") (pinfunction "A_A") (pintype "passive"))
      (node (ref "D4") (pin "A") (pinfunction "A_A") (pintype "passive"))
      (node (ref "D6") (pin "A") (pinfunction "A_A") (pintype "passive"))
      (node (ref "D8") (pin "A") (pinfunction "A_A") (pintype "passive"))
      (node (ref "MCU") (pin "11") (pinfunction "11/MOSI_11") (pintype "bidirectional"))
      (node (ref "VR1") (pin "3") (pinfunction "E_3") (pintype "passive"))
      (node (ref "VR10") (pin "3") (pinfunction "E_3") (pintype "passive"))
      (node (ref "VR11") (pin "3") (pinfunction "E_3") (pintype "passive"))
      (node (ref "VR12") (pin "3") (pinfunction "E_3") (pintype "passive"))
      (node (ref "VR13") (pin "3") (pinfunction "E_3") (pintype "passive"))
      (node (ref "VR14") (pin "3") (pinfunction "E_3") (pintype "passive"))
      (node (ref "VR15") (pin "3") (pinfunction "E_3") (pintype "passive"))
      (node (ref "VR16") (pin "3") (pinfunction "E_3") (pintype "passive"))
      (node (ref "VR2") (pin "3") (pinfunction "E_3") (pintype "passive"))
      (node (ref "VR3") (pin "3") (pinfunction "E_3") (pintype "passive"))
      (node (ref "VR4") (pin "3") (pinfunction "E_3") (pintype "passive"))
      (node (ref "VR5") (pin "3") (pinfunction "E_3") (pintype "passive"))
      (node (ref "VR6") (pin "3") (pinfunction "E_3") (pintype "passive"))
      (node (ref "VR7") (pin "3") (pinfunction "E_3") (pintype "passive"))
      (node (ref "VR8") (pin "3") (pinfunction "E_3") (pintype "passive"))
      (node (ref "VR9") (pin "3") (pinfunction "E_3") (pintype "passive"))
    )
    (net (code "63") (name "STEP2") (class "Default")
      (node (ref "MCU") (pin "12") (pinfunction "12/MISO_12") (pintype "bidirectional"))
    )
    (net (code "64") (name "STEP3") (class "Default")
      (node (ref "MCU") (pin "RESET/DAC") (pinfunction "26/A12/DAC_RESET/DAC") (pintype "power_in"))
    )
    (net (code "65") (name "STEP4") (class "Default")
      (node (ref "MCU") (pin "13") (pinfunction "13/SCK/LED_13") (pintype "bidirectional"))
    )
    (net (code "66") (name "STEP5") (class "Default")
      (node (ref "MCU") (pin "9") (pinfunction "9/RX2/PWM_9") (pintype "bidirectional"))
    )
    (net (code "67") (name "STEP6") (class "Default")
      (node (ref "MCU") (pin "10") (pinfunction "10/TX2/PWM_10") (pintype "bidirectional"))
    )
    (net (code "68") (name "STEP7") (class "Default")
      (node (ref "MCU") (pin "14/A0") (pinfunction "14/A0_14/A0") (pintype "bidirectional"))
    )
    (net (code "69") (name "STEP8") (class "Default")
      (node (ref "MCU") (pin "15/A1") (pinfunction "15/A1/T_15/A1") (pintype "bidirectional"))
    )
    (net (code "70") (name "STEP9") (class "Default")
      (node (ref "MCU") (pin "7") (pinfunction "7/RX3_7") (pintype "bidirectional"))
    )
    (net (code "71") (name "STEP10") (class "Default")
      (node (ref "MCU") (pin "8") (pinfunction "8/TX3_8") (pintype "bidirectional"))
    )
    (net (code "72") (name "STEP11") (class "Default")
      (node (ref "MCU") (pin "16/A2") (pinfunction "16/A2/PWM/T_16/A2") (pintype "bidirectional"))
    )
    (net (code "73") (name "STEP12") (class "Default")
      (node (ref "MCU") (pin "22/A8") (pinfunction "22/A8/T/PWM/SCL1_22/A8") (pintype "bidirectional"))
    )
    (net (code "74") (name "STEP13") (class "Default")
      (node (ref "MCU") (pin "6") (pinfunction "6/PWM_6") (pintype "bidirectional"))
    )
    (net (code "75") (name "STEP14") (class "Default")
      (node (ref "MCU") (pin "A11") (pinfunction "A11_A11") (pintype "bidirectional"))
    )
    (net (code "76") (name "STEP15") (class "Default")
      (node (ref "MCU") (pin "18/A4") (pinfunction "18/A4/T/SDA_18/A4") (pintype "bidirectional"))
    )
    (net (code "77") (name "STEP16") (class "Default")
      (node (ref "MCU") (pin "19/A5") (pinfunction "19/A5/T/SCL_19/A5") (pintype "bidirectional"))
    )
    (net (code "78") (name "TRIG") (class "Default")
      (node (ref "MCU") (pin "VBAT") (pinfunction "17_AT_VIN_VBAT") (pintype "bidirectional"))
      (node (ref "R18") (pin "2") (pinfunction "2_2") (pintype "passive"))
    )
    (net (code "79") (name "unconnected-(MCU-17{slash}A3{slash}PWM{slash}T-Pad17{slash}A3)") (class "Default")
      (node (ref "MCU") (pin "17/A3") (pinfunction "17/A3/PWM/T_17/A3") (pintype "bidirectional"))
    )
    (net (code "80") (name "unconnected-(MCU-PadA10)") (class "Default")
      (node (ref "MCU") (pin "A10") (pinfunction "A10_A10") (pintype "bidirectional"))
    )
    (net (code "81") (name "unconnected-(MCU-PadPGM)") (class "Default")
      (node (ref "MCU") (pin "PGM") (pinfunction "PGM_PGM") (pintype "bidirectional"))
    )
    (net (code "82") (name "unconnected-(U1-SWITCH-PadP$2_SWITCH)") (class "Default")
      (node (ref "U1") (pin "P$2_SWITCH") (pinfunction "SWITCH_P$2_SWITCH") (pintype "passive"))
    )
    (net (code "83") (name "unconnected-(U2-SWITCH-PadP$2_SWITCH)") (class "Default")
      (node (ref "U2") (pin "P$2_SWITCH") (pinfunction "SWITCH_P$2_SWITCH") (pintype "passive"))
    )
    (net (code "84") (name "unconnected-(U11-SWITCH-PadP$2_SWITCH)") (class "Default")
      (node (ref "U11") (pin "P$2_SWITCH") (pinfunction "SWITCH_P$2_SWITCH") (pintype "passive"))
    )
  )
)
